# P1.net
KiCad netlist of a schematic drawn in Altium Designer
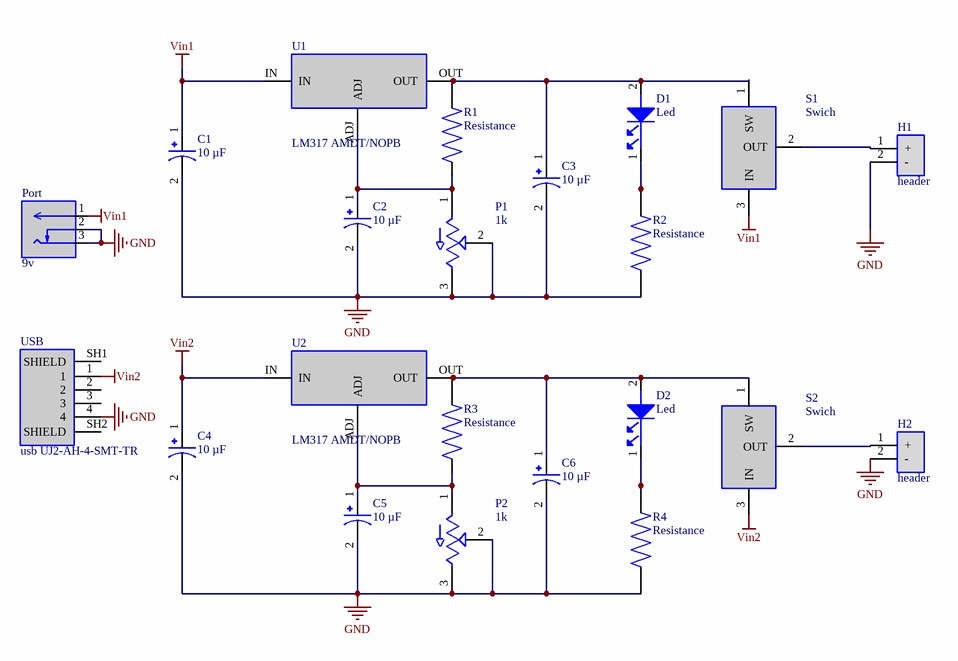
[diagram p0: P1.SchDoc]

(export (version "E")
  (design (tool "Eeschema 10.0.6"))
  (components
    (comp (ref "C1")
      (value "10 µF")
      (footprint "capacitores")
      (fields
        (field (name "MANUFACTURER") "Kyocera AVX")
        (field (name "MANUFACTURER PART NUMBER") "TAJA106K016SNJ")
        (field (name "TOLERANCE") "10%")
      )
      (libsource (lib "P1_Schlib1") (part "capacitores TAJA106K016SNJ"))
    )
    (comp (ref "C2")
      (value "10 µF")
      (footprint "capacitores")
      (fields
        (field (name "MANUFACTURER") "Kyocera AVX")
        (field (name "MANUFACTURER PART NUMBER") "TAJA106K016SNJ")
        (field (name "TOLERANCE") "10%")
      )
      (libsource (lib "P1_Schlib1") (part "capacitores TAJA106K016SNJ"))
    )
    (comp (ref "C3")
      (value "10 µF")
      (footprint "capacitores")
      (fields
        (field (name "MANUFACTURER") "Kyocera AVX")
        (field (name "MANUFACTURER PART NUMBER") "TAJA106K016SNJ")
        (field (name "TOLERANCE") "10%")
      )
      (libsource (lib "P1_Schlib1") (part "capacitores TAJA106K016SNJ"))
    )
    (comp (ref "C4")
      (value "10 µF")
      (footprint "capacitores")
      (fields
        (field (name "MANUFACTURER") "Kyocera AVX")
        (field (name "MANUFACTURER PART NUMBER") "TAJA106K016SNJ")
        (field (name "TOLERANCE") "10%")
      )
      (libsource (lib "P1_Schlib1") (part "capacitores TAJA106K016SNJ"))
    )
    (comp (ref "C5")
      (value "10 µF")
      (footprint "capacitores")
      (fields
        (field (name "MANUFACTURER") "Kyocera AVX")
        (field (name "MANUFACTURER PART NUMBER") "TAJA106K016SNJ")
        (field (name "TOLERANCE") "10%")
      )
      (libsource (lib "P1_Schlib1") (part "capacitores TAJA106K016SNJ"))
    )
    (comp (ref "C6")
      (value "10 µF")
      (footprint "capacitores")
      (fields
        (field (name "MANUFACTURER") "Kyocera AVX")
        (field (name "MANUFACTURER PART NUMBER") "TAJA106K016SNJ")
        (field (name "TOLERANCE") "10%")
      )
      (libsource (lib "P1_Schlib1") (part "capacitores TAJA106K016SNJ"))
    )
    (comp (ref "D1")
      (value "Led")
      (footprint "leds")
      (description "DIALIGHT   5988020107F   LED, RED ORANGE, 150MCD, 630NM")
      (fields
        (field (name "MANUFACTURER") "Dialight")
        (field (name "MANUFACTURER PART NUMBER") "598-8020-107F")
      )
      (libsource (lib "P1_Schlib1") (part "598-8020-107F"))
    )
    (comp (ref "D2")
      (value "Led")
      (footprint "leds")
      (description "DIALIGHT   5988020107F   LED, RED ORANGE, 150MCD, 630NM")
      (fields
        (field (name "MANUFACTURER") "Dialight")
        (field (name "MANUFACTURER PART NUMBER") "598-8020-107F")
      )
      (libsource (lib "P1_Schlib1") (part "598-8020-107F"))
    )
    (comp (ref "H1")
      (value "header")
      (footprint "headers")
      (description "02 MODII HDR DRST B/A 100 W/HD")
      (fields
        (field (name "MANUFACTURER") "TE Connectivity")
        (field (name "MANUFACTURER PART NUMBER") "5-146268-1")
      )
      (libsource (lib "P1_Schlib1") (part "header 5-146268-1"))
    )
    (comp (ref "H2")
      (value "header")
      (footprint "headers")
      (description "02 MODII HDR DRST B/A 100 W/HD")
      (fields
        (field (name "MANUFACTURER") "TE Connectivity")
        (field (name "MANUFACTURER PART NUMBER") "5-146268-1")
      )
      (libsource (lib "P1_Schlib1") (part "header 5-146268-1"))
    )
    (comp (ref "P1")
      (value "1k")
      (footprint "potenciometro")
      (description "BI TECHNOLOGIES / TT ELECTRONICS         35WR1KLFTR            TRIMMER CERMET,  3MM 1K")
      (fields (field (name "MANUFACTURER") "TT BI") (field (name "MANUFACTURER PART NUMBER") "35WR1KLFTR"))
      (libsource (lib "P1_Schlib1") (part "potenciometros 35WR1KLFTR"))
    )
    (comp (ref "P2")
      (value "1k")
      (footprint "potenciometro")
      (description "BI TECHNOLOGIES / TT ELECTRONICS         35WR1KLFTR            TRIMMER CERMET,  3MM 1K")
      (fields (field (name "MANUFACTURER") "TT BI") (field (name "MANUFACTURER PART NUMBER") "35WR1KLFTR"))
      (libsource (lib "P1_Schlib1") (part "potenciometros 35WR1KLFTR"))
    )
    (comp (ref "Port")
      (value "9v")
      (footprint "puerto 9v")
      (description "Conn DC Power RCP 2 POS Solder RA Thru-Hole 3 Terminal 1 Port")
      (fields (field (name "MANUFACTURER") "Tensility") (field (name "MANUFACTURER PART NUMBER") "54-00133"))
      (libsource (lib "P1_Schlib1") (part "54-00133"))
    )
    (comp (ref "R1")
      (value "Resistance")
      (footprint "resistencias")
      (fields
        (field (name "MANUFACTURER") "Vishay")
        (field (name "MANUFACTURER PART NUMBER") "CRCW0805121RFKEA")
        (field (name "TOLERANCE") "1%")
      )
      (libsource (lib "P1_Schlib1") (part "CRCW0805121RFKEA"))
    )
    (comp (ref "R2")
      (value "Resistance")
      (footprint "resistencias")
      (description "RES SMD 470 OHM 5% 0.4W 0805")
      (fields
        (field (name "MANUFACTURER") "Vishay Dale")
        (field (name "MANUFACTURER PART NUMBER") "RCS0805470RJNEA")
      )
      (libsource (lib "P1_Schlib1") (part "RCS0805470RJNEA"))
    )
    (comp (ref "R3")
      (value "Resistance")
      (footprint "resistencias")
      (fields
        (field (name "MANUFACTURER") "Vishay")
        (field (name "MANUFACTURER PART NUMBER") "CRCW0805121RFKEA")
        (field (name "TOLERANCE") "1%")
      )
      (libsource (lib "P1_Schlib1") (part "CRCW0805121RFKEA"))
    )
    (comp (ref "R4")
      (value "Resistance")
      (footprint "resistencias")
      (description "RES SMD 470 OHM 5% 0.4W 0805")
      (fields
        (field (name "MANUFACTURER") "Vishay Dale")
        (field (name "MANUFACTURER PART NUMBER") "RCS0805470RJNEA")
      )
      (libsource (lib "P1_Schlib1") (part "RCS0805470RJNEA"))
    )
    (comp (ref "S1")
      (value "Swich")
      (footprint "switchs")
      (description "Switch Slide DIP SPDT 100MA 6V")
      (fields
        (field (name "MANUFACTURER") "Nidec Copal")
        (field (name "MANUFACTURER PART NUMBER") "CJS-1201TB")
      )
      (libsource (lib "P1_Schlib1") (part "switch CJS-1201TB"))
    )
    (comp (ref "S2")
      (value "Swich")
      (footprint "switchs")
      (description "Switch Slide DIP SPDT 100MA 6V")
      (fields
        (field (name "MANUFACTURER") "Nidec Copal")
        (field (name "MANUFACTURER PART NUMBER") "CJS-1201TB")
      )
      (libsource (lib "P1_Schlib1") (part "switch CJS-1201TB"))
    )
    (comp (ref "U1")
      (value "LM317 AMDT/NOPB")
      (footprint "Lm317")
      (description "IC REG LIN POS ADJ 1.5A TO252-3")
      (fields
        (field (name "MANUFACTURER") "TI National Semiconductor")
        (field (name "MANUFACTURER PART NUMBER") "LM317AMDT/NOPB")
      )
      (libsource (lib "P1_Schlib1") (part "LM317 AMDT/NOPB"))
    )
    (comp (ref "U2")
      (value "LM317 AMDT/NOPB")
      (footprint "Lm317")
      (description "IC REG LIN POS ADJ 1.5A TO252-3")
      (fields
        (field (name "MANUFACTURER") "TI National Semiconductor")
        (field (name "MANUFACTURER PART NUMBER") "LM317AMDT/NOPB")
      )
      (libsource (lib "P1_Schlib1") (part "LM317 AMDT/NOPB"))
    )
    (comp (ref "USB")
      (value "usb UJ2-AH-4-SMT-TR")
      (footprint "usb")
      (description "USB jack 2.0, standard A type, 4 pin, horizontal, 30 µin plating, SMT")
      (fields (field (name "MANUFACTURER") "CUI") (field (name "MANUFACTURER PART NUMBER") "UJ2-AH-4-SMT-TR"))
      (libsource (lib "P1_Schlib1") (part "usb UJ2-AH-4-SMT-TR"))
    )
  )
  (nets
    (net (code "1") (name "GND") (class "Default")
      (node (ref "C1") (pin "2") (pinfunction "2_2") (pintype "passive"))
      (node (ref "C2") (pin "2") (pinfunction "2_2") (pintype "passive"))
      (node (ref "C3") (pin "2") (pinfunction "2_2") (pintype "passive"))
      (node (ref "C4") (pin "2") (pinfunction "2_2") (pintype "passive"))
      (node (ref "C5") (pin "2") (pinfunction "2_2") (pintype "passive"))
      (node (ref "C6") (pin "2") (pinfunction "2_2") (pintype "passive"))
      (node (ref "H1") (pin "2") (pinfunction "-_2") (pintype "passive"))
      (node (ref "H2") (pin "2") (pinfunction "-_2") (pintype "passive"))
      (node (ref "P1") (pin "2") (pinfunction "W_2") (pintype "passive"))
      (node (ref "P1") (pin "3") (pinfunction "CW_3") (pintype "passive"))
      (node (ref "P2") (pin "2") (pinfunction "W_2") (pintype "passive"))
      (node (ref "P2") (pin "3") (pinfunction "CW_3") (pintype "passive"))
      (node (ref "Port") (pin "2") (pinfunction "SHUNT_2") (pintype "passive"))
      (node (ref "Port") (pin "3") (pinfunction "TIP_3") (pintype "passive"))
      (node (ref "R2") (pin "1") (pinfunction "1_1") (pintype "passive"))
      (node (ref "R4") (pin "1") (pinfunction "1_1") (pintype "passive"))
      (node (ref "USB") (pin "4") (pinfunction "4_4") (pintype "passive"))
    )
    (net (code "2") (name "Net-(D1-Pad1)") (class "Default")
      (node (ref "D1") (pin "1") (pinfunction "1_1") (pintype "passive"))
      (node (ref "R2") (pin "2") (pinfunction "2_2") (pintype "passive"))
    )
    (net (code "3") (name "Net-(D2-Pad1)") (class "Default")
      (node (ref "D2") (pin "1") (pinfunction "1_1") (pintype "passive"))
      (node (ref "R4") (pin "2") (pinfunction "2_2") (pintype "passive"))
    )
    (net (code "4") (name "Net-(H1-+)") (class "Default")
      (node (ref "H1") (pin "1") (pinfunction "+_1") (pintype "passive"))
      (node (ref "S1") (pin "2") (pinfunction "OUT_2") (pintype "power_in"))
    )
    (net (code "5") (name "Net-(H2-+)") (class "Default")
      (node (ref "H2") (pin "1") (pinfunction "+_1") (pintype "passive"))
      (node (ref "S2") (pin "2") (pinfunction "OUT_2") (pintype "power_in"))
    )
    (net (code "6") (name "Net-(P1-CCW)") (class "Default")
      (node (ref "C2") (pin "1") (pinfunction "1_1") (pintype "passive"))
      (node (ref "P1") (pin "1") (pinfunction "CCW_1") (pintype "passive"))
      (node (ref "R1") (pin "1") (pinfunction "1_1") (pintype "passive"))
      (node (ref "U1") (pin "ADJ") (pinfunction "ADJ_ADJ") (pintype "power_in"))
    )
    (net (code "7") (name "Net-(P2-CCW)") (class "Default")
      (node (ref "C5") (pin "1") (pinfunction "1_1") (pintype "passive"))
      (node (ref "P2") (pin "1") (pinfunction "CCW_1") (pintype "passive"))
      (node (ref "R3") (pin "1") (pinfunction "1_1") (pintype "passive"))
      (node (ref "U2") (pin "ADJ") (pinfunction "ADJ_ADJ") (pintype "power_in"))
    )
    (net (code "8") (name "Net-(S1-SW)") (class "Default")
      (node (ref "C3") (pin "1") (pinfunction "1_1") (pintype "passive"))
      (node (ref "D1") (pin "2") (pinfunction "2_2") (pintype "passive"))
      (node (ref "R1") (pin "2") (pinfunction "2_2") (pintype "passive"))
      (node (ref "S1") (pin "1") (pinfunction "SW_1") (pintype "power_in"))
      (node (ref "U1") (pin "OUT") (pinfunction "OUT_OUT") (pintype "power_in"))
    )
    (net (code "9") (name "Net-(S2-SW)") (class "Default")
      (node (ref "C6") (pin "1") (pinfunction "1_1") (pintype "passive"))
      (node (ref "D2") (pin "2") (pinfunction "2_2") (pintype "passive"))
      (node (ref "R3") (pin "2") (pinfunction "2_2") (pintype "passive"))
      (node (ref "S2") (pin "1") (pinfunction "SW_1") (pintype "power_in"))
      (node (ref "U2") (pin "OUT") (pinfunction "OUT_OUT") (pintype "power_in"))
    )
    (net (code "10") (name "Vin1") (class "Default")
      (node (ref "C1") (pin "1") (pinfunction "1_1") (pintype "passive"))
      (node (ref "Port") (pin "1") (pinfunction "PIN_1") (pintype "passive"))
      (node (ref "S1") (pin "3") (pinfunction "IN_3") (pintype "power_in"))
      (node (ref "U1") (pin "IN") (pinfunction "IN_IN") (pintype "power_in"))
    )
    (net (code "11") (name "Vin2") (class "Default")
      (node (ref "C4") (pin "1") (pinfunction "1_1") (pintype "passive"))
      (node (ref "S2") (pin "3") (pinfunction "IN_3") (pintype "power_in"))
      (node (ref "U2") (pin "IN") (pinfunction "IN_IN") (pintype "power_in"))
      (node (ref "USB") (pin "1") (pinfunction "1_1") (pintype "passive"))
    )
    (net (code "12") (name "unconnected-(USB-Pad2)") (class "Default")
      (node (ref "USB") (pin "2") (pinfunction "2_2") (pintype "passive"))
    )
    (net (code "13") (name "unconnected-(USB-Pad3)") (class "Default")
      (node (ref "USB") (pin "3") (pinfunction "3_3") (pintype "passive"))
    )
    (net (code "14") (name "unconnected-(USB-SHIELD-PadSH1)") (class "Default")
      (node (ref "USB") (pin "SH1") (pinfunction "SHIELD_SH1") (pintype "passive"))
    )
    (net (code "15") (name "unconnected-(USB-SHIELD-PadSH2)") (class "Default")
      (node (ref "USB") (pin "SH2") (pinfunction "SHIELD_SH2") (pintype "passive"))
    )
  )
)
